# 01_Power.net
KiCad netlist of a schematic drawn in Altium Designer
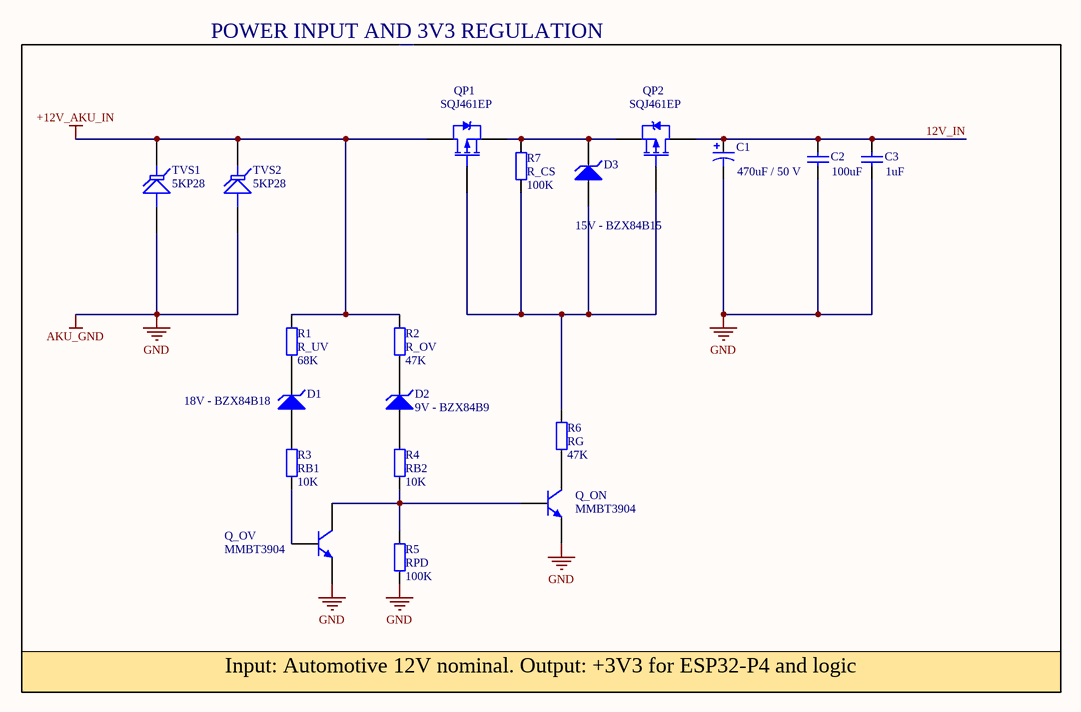
[diagram p0: 01_Power.SchDoc]

(export (version "E")
  (design (tool "Eeschema 10.0.6"))
  (components
    (comp (ref "C1")
      (value "470uF / 50 V")
      (footprint "RB7.6-15")
      (description "Polarized Capacitor (Radial)")
      (fields (field (name "Comment") "Bulk Electrolytic") (field (name "PUBLISHER") "Altium Limited"))
      (libsource (lib "Miscellaneous Devices") (part "Cap Pol1"))
    )
    (comp (ref "C2")
      (value "100uF")
      (footprint "RAD-0.3")
      (description "Capacitor")
      (fields (field (name "Comment") "Cap") (field (name "PUBLISHER") "Altium Limited"))
      (libsource (lib "Miscellaneous Devices") (part "Cap"))
    )
    (comp (ref "C3")
      (value "1uF")
      (footprint "RAD-0.3")
      (description "Capacitor")
      (fields (field (name "Comment") "Cap") (field (name "PUBLISHER") "Altium Limited"))
      (libsource (lib "Miscellaneous Devices") (part "Cap"))
    )
    (comp (ref "D1")
      (value "18V - BZX84B18")
      (footprint "DIODE-0.7")
      (description "Zener Diode")
      (fields (field (name "PUBLISHER") "Altium Limited"))
      (libsource (lib "Miscellaneous Devices") (part "D Zener"))
    )
    (comp (ref "D2")
      (value "9V - BZX84B9")
      (footprint "DIODE-0.7")
      (description "Zener Diode")
      (fields (field (name "PUBLISHER") "Altium Limited"))
      (libsource (lib "Miscellaneous Devices") (part "D Zener"))
    )
    (comp (ref "D3")
      (value "15V - BZX84B15")
      (footprint "DIODE-0.7")
      (description "Zener Diode")
      (fields (field (name "PUBLISHER") "Altium Limited"))
      (libsource (lib "Miscellaneous Devices") (part "D Zener"))
    )
    (comp (ref "QP1")
      (value "SQJ461EP")
      (footprint "SO8_L")
      (description "VDS >= 60V P-Channel Power MOSFET with body diode. Direction Aku -> CS")
      (fields (field (name "PUBLISHER") "Altium Limited"))
      (libsource (lib "Miscellaneous Devices") (part "PMOS-2"))
    )
    (comp (ref "QP2")
      (value "SQJ461EP")
      (footprint "SO8_L")
      (description "VDS >= 60V P-Channel Power MOSFET with body diode. Direction  , CS  <- DC Regulator")
      (fields (field (name "PUBLISHER") "Altium Limited"))
      (libsource (lib "Miscellaneous Devices") (part "PMOS-2"))
    )
    (comp (ref "Q_ON")
      (value "MMBT3904")
      (footprint "SOT-23B_L")
      (description "NPN Bipolar Transistor")
      (fields (field (name "PUBLISHER") "Altium Limited"))
      (libsource (lib "Miscellaneous Devices") (part "QNPN"))
    )
    (comp (ref "Q_OV")
      (value "MMBT3904")
      (footprint "SOT-23B_L")
      (description "NPN Bipolar Transistor")
      (fields (field (name "PUBLISHER") "Altium Limited"))
      (libsource (lib "Miscellaneous Devices") (part "QNPN"))
    )
    (comp (ref "R1")
      (value "R_UV")
      (footprint "AXIAL-0.4")
      (description "Resistor")
      (fields (field (name "ALTIUM_VALUE") "68K") (field (name "PUBLISHER") "Altium Limited"))
      (libsource (lib "Miscellaneous Devices") (part "Res2"))
    )
    (comp (ref "R2")
      (value "R_OV")
      (footprint "AXIAL-0.4")
      (description "Resistor")
      (fields (field (name "ALTIUM_VALUE") "47K") (field (name "PUBLISHER") "Altium Limited"))
      (libsource (lib "Miscellaneous Devices") (part "Res2"))
    )
    (comp (ref "R3")
      (value "RB1")
      (footprint "AXIAL-0.4")
      (description "Resistor")
      (fields (field (name "ALTIUM_VALUE") "10K") (field (name "PUBLISHER") "Altium Limited"))
      (libsource (lib "Miscellaneous Devices") (part "Res2"))
    )
    (comp (ref "R4")
      (value "RB2")
      (footprint "AXIAL-0.4")
      (description "Resistor")
      (fields (field (name "ALTIUM_VALUE") "10K") (field (name "PUBLISHER") "Altium Limited"))
      (libsource (lib "Miscellaneous Devices") (part "Res2"))
    )
    (comp (ref "R5")
      (value "RPD")
      (footprint "AXIAL-0.4")
      (description "Resistor")
      (fields (field (name "ALTIUM_VALUE") "100K") (field (name "PUBLISHER") "Altium Limited"))
      (libsource (lib "Miscellaneous Devices") (part "Res2"))
    )
    (comp (ref "R6")
      (value "RG")
      (footprint "AXIAL-0.4")
      (description "Resistor")
      (fields (field (name "ALTIUM_VALUE") "47K") (field (name "PUBLISHER") "Altium Limited"))
      (libsource (lib "Miscellaneous Devices") (part "Res2"))
    )
    (comp (ref "R7")
      (value "R_CS")
      (footprint "AXIAL-0.4")
      (description "Resistor")
      (fields (field (name "ALTIUM_VALUE") "100K") (field (name "PUBLISHER") "Altium Limited"))
      (libsource (lib "Miscellaneous Devices") (part "Res2"))
    )
    (comp (ref "TVS1")
      (value "5KP28")
      (footprint "DO-7")
      (description "50V clamp - Transient Voltage Suppression (TVS) Diode")
      (fields (field (name "PUBLISHER") "Altium Limited"))
      (libsource (lib "Miscellaneous Devices") (part "Tranzorb"))
    )
    (comp (ref "TVS2")
      (value "5KP28")
      (footprint "DO-7")
      (description "50V  clamp - Transient Voltage Suppression (TVS) Diode")
      (fields (field (name "PUBLISHER") "Altium Limited"))
      (libsource (lib "Miscellaneous Devices") (part "Tranzorb"))
    )
  )
  (nets
    (net (code "1") (name "+12V_AKU_IN") (class "Default")
      (node (ref "QP1") (pin "2") (pinfunction "D_2") (pintype "passive"))
      (node (ref "R1") (pin "2") (pinfunction "2_2") (pintype "passive"))
      (node (ref "R2") (pin "2") (pinfunction "2_2") (pintype "passive"))
      (node (ref "TVS1") (pin "2") (pinfunction "K_2") (pintype "passive"))
      (node (ref "TVS2") (pin "2") (pinfunction "K_2") (pintype "passive"))
    )
    (net (code "2") (name "/12V_IN") (class "Default")
      (node (ref "C1") (pin "1") (pinfunction "1_1") (pintype "passive"))
      (node (ref "C2") (pin "2") (pinfunction "2_2") (pintype "passive"))
      (node (ref "C3") (pin "2") (pinfunction "2_2") (pintype "passive"))
      (node (ref "QP2") (pin "2") (pinfunction "D_2") (pintype "passive"))
    )
    (net (code "3") (name "AKU_GND") (class "Default")
      (node (ref "C1") (pin "2") (pinfunction "2_2") (pintype "passive"))
      (node (ref "C2") (pin "1") (pinfunction "1_1") (pintype "passive"))
      (node (ref "C3") (pin "1") (pinfunction "1_1") (pintype "passive"))
      (node (ref "Q_ON") (pin "3") (pinfunction "E_3") (pintype "passive"))
      (node (ref "Q_OV") (pin "3") (pinfunction "E_3") (pintype "passive"))
      (node (ref "R5") (pin "1") (pinfunction "1_1") (pintype "passive"))
      (node (ref "TVS1") (pin "1") (pinfunction "A_1") (pintype "passive"))
      (node (ref "TVS2") (pin "1") (pinfunction "A_1") (pintype "passive"))
    )
    (net (code "4") (name "Net-(D1-A)") (class "Default")
      (node (ref "D1") (pin "1") (pinfunction "A_1") (pintype "passive"))
      (node (ref "R3") (pin "2") (pinfunction "2_2") (pintype "passive"))
    )
    (net (code "5") (name "Net-(D1-K)") (class "Default")
      (node (ref "D1") (pin "2") (pinfunction "K_2") (pintype "passive"))
      (node (ref "R1") (pin "1") (pinfunction "1_1") (pintype "passive"))
    )
    (net (code "6") (name "Net-(D2-A)") (class "Default")
      (node (ref "D2") (pin "1") (pinfunction "A_1") (pintype "passive"))
      (node (ref "R4") (pin "2") (pinfunction "2_2") (pintype "passive"))
    )
    (net (code "7") (name "Net-(D2-K)") (class "Default")
      (node (ref "D2") (pin "2") (pinfunction "K_2") (pintype "passive"))
      (node (ref "R2") (pin "1") (pinfunction "1_1") (pintype "passive"))
    )
    (net (code "8") (name "Net-(D3-A)") (class "Default")
      (node (ref "D3") (pin "1") (pinfunction "A_1") (pintype "passive"))
      (node (ref "QP1") (pin "1") (pinfunction "G_1") (pintype "passive"))
      (node (ref "QP2") (pin "1") (pinfunction "G_1") (pintype "passive"))
      (node (ref "R6") (pin "2") (pinfunction "2_2") (pintype "passive"))
      (node (ref "R7") (pin "1") (pinfunction "1_1") (pintype "passive"))
    )
    (net (code "9") (name "Net-(D3-K)") (class "Default")
      (node (ref "D3") (pin "2") (pinfunction "K_2") (pintype "passive"))
      (node (ref "QP1") (pin "3") (pinfunction "S_3") (pintype "passive"))
      (node (ref "QP2") (pin "3") (pinfunction "S_3") (pintype "passive"))
      (node (ref "R7") (pin "2") (pinfunction "2_2") (pintype "passive"))
    )
    (net (code "10") (name "Net-(Q_ON-B)") (class "Default")
      (node (ref "Q_ON") (pin "2") (pinfunction "B_2") (pintype "passive"))
      (node (ref "Q_OV") (pin "1") (pinfunction "C_1") (pintype "passive"))
      (node (ref "R4") (pin "1") (pinfunction "1_1") (pintype "passive"))
      (node (ref "R5") (pin "2") (pinfunction "2_2") (pintype "passive"))
    )
    (net (code "11") (name "Net-(Q_ON-C)") (class "Default")
      (node (ref "Q_ON") (pin "1") (pinfunction "C_1") (pintype "passive"))
      (node (ref "R6") (pin "1") (pinfunction "1_1") (pintype "passive"))
    )
    (net (code "12") (name "Net-(Q_OV-B)") (class "Default")
      (node (ref "Q_OV") (pin "2") (pinfunction "B_2") (pintype "passive"))
      (node (ref "R3") (pin "1") (pinfunction "1_1") (pintype "passive"))
    )
  )
)
